# DCDC_12V.net
KiCad netlist of a schematic drawn in Altium Designer
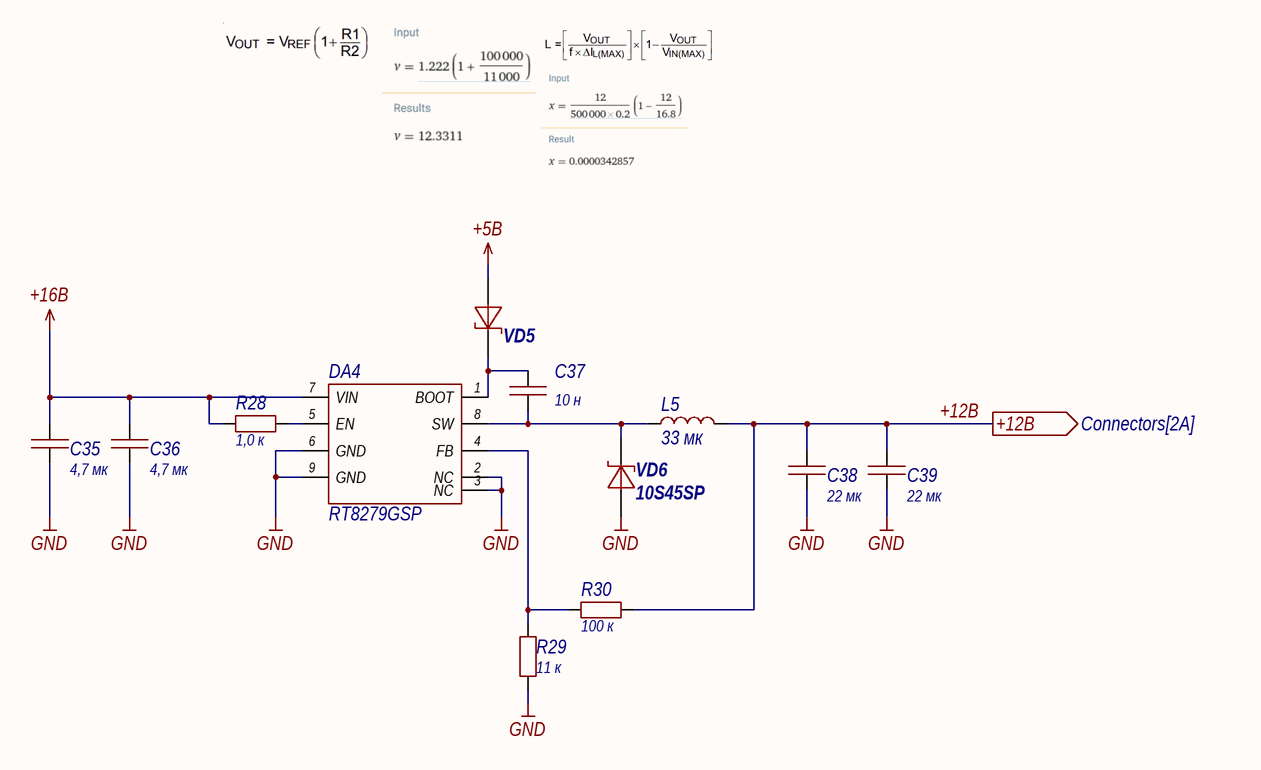
[diagram p0: DCDC_12V.SchDoc]

(export (version "E")
  (design (tool "Eeschema 10.0.6"))
  (components
    (comp (ref "C35")
      (value "4,7 мк")
      (footprint "1206C")
      (description "Конденсатор")
      (fields (field (name "PART NUMBER") "Capacitor_4,7u_10_50V_X7R_1206C") (field (name "TOLERANCE") "0,1"))
      (libsource (lib "Hydrolib") (part "Capacitor"))
    )
    (comp (ref "C36")
      (value "4,7 мк")
      (footprint "1206C")
      (description "Конденсатор")
      (fields (field (name "PART NUMBER") "Capacitor_4,7u_10_50V_X7R_1206C") (field (name "TOLERANCE") "0,1"))
      (libsource (lib "Hydrolib") (part "Capacitor"))
    )
    (comp (ref "C37")
      (value "10 н")
      (footprint "0603C")
      (description "Конденсатор")
      (fields (field (name "PART NUMBER") "Capacitor_10n_10_50V_X7R_0603C") (field (name "TOLERANCE") "0,1"))
      (libsource (lib "Hydrolib") (part "Capacitor"))
    )
    (comp (ref "C38")
      (value "22 мк")
      (footprint "1210C")
      (description "Конденсатор")
      (fields (field (name "PART NUMBER") "Capacitor_22u_10_25V_X7R_1210C") (field (name "TOLERANCE") "0,1"))
      (libsource (lib "Hydrolib") (part "Capacitor"))
    )
    (comp (ref "C39")
      (value "22 мк")
      (footprint "1210C")
      (description "Конденсатор")
      (fields (field (name "PART NUMBER") "Capacitor_22u_10_25V_X7R_1210C") (field (name "TOLERANCE") "0,1"))
      (libsource (lib "Hydrolib") (part "Capacitor"))
    )
    (comp (ref "DA4")
      (value "RT8279GSP")
      (footprint "8SOP(Exposed_Pad)")
      (description "Преобразователь постоянного тока понижающий подстраиваемый выход 5А")
      (libsource (lib "Hydrolib") (part "RT8279GSP"))
    )
    (comp (ref "L5")
      (value "33 мк")
      (footprint "IHLP-4040")
      (description "ЧИП-индуктивность экранированная 33мкГн ±20% 4,4A 94,5мОм 4040")
      (fields (field (name "PART NUMBER") "IHLP4040DZER330M11"))
      (libsource (lib "Hydrolib") (part "Inductance"))
    )
    (comp (ref "R28")
      (value "1,0 к")
      (footprint "0603R")
      (description "Резистор номиналом 1,0 кОм и точностью 1%")
      (fields (field (name "PART NUMBER") "Resistor_1.0k_1_0603") (field (name "TOLERANCE") "1%"))
      (libsource (lib "") (part "Resistor_1"))
    )
    (comp (ref "R29")
      (value "11 к")
      (footprint "0603R")
      (description "Резистор номиналом 11 кОм и точностью 1%")
      (fields (field (name "PART NUMBER") "Resistor_11k_1_0603") (field (name "TOLERANCE") "1%"))
      (libsource (lib "") (part "Resistor_2"))
    )
    (comp (ref "R30")
      (value "100 к")
      (footprint "0603R")
      (description "Резистор номиналом 100 кОм и точностью 1%")
      (fields (field (name "PART NUMBER") "Resistor_100k_1_0603") (field (name "TOLERANCE") "1%"))
      (libsource (lib "Hydrolib") (part "Resistor"))
    )
    (comp (ref "VD5")
      (value "BAT54WS")
      (footprint "SOD-323")
      (description "Диод шоттки на 30 В, ном. ток 0.2 А")
      (libsource (lib "Hydrolib") (part "Schottky_diode"))
    )
    (comp (ref "VD6")
      (value "10S45SP")
      (footprint "TO-277")
      (description "Диод шоттки на 45 В, ном. ток 10 А")
      (libsource (lib "Hydrolib") (part "Schottky_diode"))
    )
  )
  (nets
    (net (code "1") (name "+5В") (class "Default")
      (node (ref "VD5") (pin "1") (pinfunction "1_1") (pintype "passive"))
    )
    (net (code "2") (name "+16В") (class "Default")
      (node (ref "C35") (pin "2") (pinfunction "2_2") (pintype "passive"))
      (node (ref "C36") (pin "2") (pinfunction "2_2") (pintype "passive"))
      (node (ref "DA4") (pin "7") (pinfunction "VIN_7") (pintype "passive"))
      (node (ref "R28") (pin "2") (pinfunction "2_2") (pintype "passive"))
    )
    (net (code "3") (name "/+12В") (class "Default")
      (node (ref "C38") (pin "2") (pinfunction "2_2") (pintype "passive"))
      (node (ref "C39") (pin "2") (pinfunction "2_2") (pintype "passive"))
      (node (ref "L5") (pin "2") (pinfunction "2_2") (pintype "passive"))
      (node (ref "R30") (pin "2") (pinfunction "2_2") (pintype "passive"))
    )
    (net (code "4") (name "GND") (class "Default")
      (node (ref "C35") (pin "1") (pinfunction "1_1") (pintype "passive"))
      (node (ref "C36") (pin "1") (pinfunction "1_1") (pintype "passive"))
      (node (ref "C38") (pin "1") (pinfunction "1_1") (pintype "passive"))
      (node (ref "C39") (pin "1") (pinfunction "1_1") (pintype "passive"))
      (node (ref "DA4") (pin "2") (pinfunction "NC_2") (pintype "passive"))
      (node (ref "DA4") (pin "3") (pinfunction "NC_3") (pintype "passive"))
      (node (ref "DA4") (pin "6") (pinfunction "GND_6") (pintype "passive"))
      (node (ref "DA4") (pin "9") (pinfunction "GND_9") (pintype "passive"))
      (node (ref "R29") (pin "1") (pinfunction "1_1") (pintype "passive"))
      (node (ref "VD6") (pin "1") (pinfunction "1_1") (pintype "passive"))
    )
    (net (code "5") (name "Net-(DA4-BOOT)") (class "Default")
      (node (ref "C37") (pin "2") (pinfunction "2_2") (pintype "passive"))
      (node (ref "DA4") (pin "1") (pinfunction "BOOT_1") (pintype "passive"))
      (node (ref "VD5") (pin "2") (pinfunction "2_2") (pintype "passive"))
    )
    (net (code "6") (name "Net-(DA4-EN)") (class "Default")
      (node (ref "DA4") (pin "5") (pinfunction "EN_5") (pintype "passive"))
      (node (ref "R28") (pin "1") (pinfunction "1_1") (pintype "passive"))
    )
    (net (code "7") (name "Net-(DA4-FB)") (class "Default")
      (node (ref "DA4") (pin "4") (pinfunction "FB_4") (pintype "passive"))
      (node (ref "R29") (pin "2") (pinfunction "2_2") (pintype "passive"))
      (node (ref "R30") (pin "1") (pinfunction "1_1") (pintype "passive"))
    )
    (net (code "8") (name "Net-(DA4-SW)") (class "Default")
      (node (ref "C37") (pin "1") (pinfunction "1_1") (pintype "passive"))
      (node (ref "DA4") (pin "8") (pinfunction "SW_8") (pintype "passive"))
      (node (ref "L5") (pin "1") (pinfunction "1_1") (pintype "passive"))
      (node (ref "VD6") (pin "2") (pinfunction "2_2") (pintype "passive"))
    )
  )
)
